# Microcontroller.net
KiCad netlist of a schematic drawn in Altium Designer
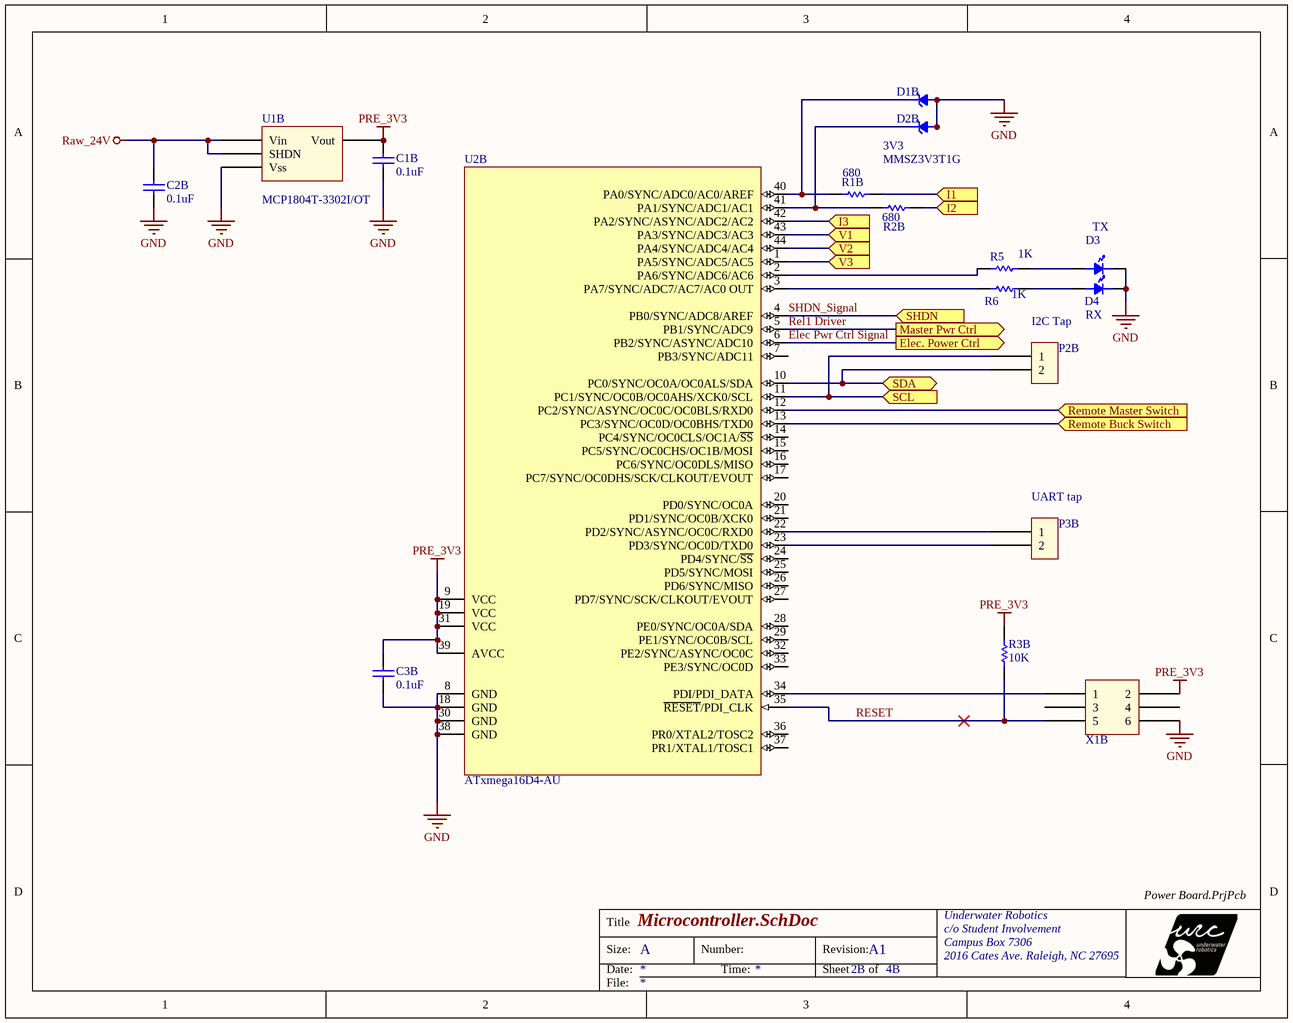
[diagram p0: Microcontroller.SchDoc]

(export (version "E")
  (design (tool "Eeschema 10.0.6"))
  (components
    (comp (ref "C1B")
      (value "0.1uF")
      (footprint "C0805")
      (description "Ceramic MLCC, AVX, X5R Dielectric")
      (fields
        (field (name "MANUFACTURER PART NUMBER") "08055C104JAT2A")
        (field (name "Comment") "0.1uF, C0805, AVX")
      )
      (libsource (lib "Capacitors SchLib") (part "0.1uF, C0805, AVX"))
    )
    (comp (ref "C2B")
      (value "0.1uF")
      (footprint "C0805")
      (description "Ceramic MLCC, AVX, X5R Dielectric")
      (fields
        (field (name "MANUFACTURER PART NUMBER") "08055C104JAT2A")
        (field (name "Comment") "0.1uF, C0805, AVX")
      )
      (libsource (lib "Capacitors SchLib") (part "0.1uF, C0805, AVX"))
    )
    (comp (ref "C3B")
      (value "0.1uF")
      (footprint "C0805")
      (description "Ceramic MLCC, AVX, X5R Dielectric")
      (fields
        (field (name "MANUFACTURER PART NUMBER") "08055C104JAT2A")
        (field (name "Comment") "0.1uF, C0805, AVX")
      )
      (libsource (lib "Capacitors SchLib") (part "0.1uF, C0805, AVX"))
    )
    (comp (ref "D1B")
      (value "3V3")
      (footprint "ONSC-SOD123-2-498_A_V")
      (description "3V3 Zener Diode")
      (fields
        (field (name "MANUFACTURER PART NUMBER") "MMSZ3V3T1G")
        (field (name "Comment") "MMSZ3V3T1G, 3V3 Zener Diode")
      )
      (libsource (lib "URC") (part "MMSZ3V3T1G, 3V3 Zener Diode"))
    )
    (comp (ref "D2B")
      (value "MMSZ3V3T1G, 3V3 Zener Diode")
      (footprint "ONSC-SOD123-2-498_A_V")
      (description "3V3 Zener Diode")
      (fields (field (name "MANUFACTURER PART NUMBER") "MMSZ3V3T1G"))
      (libsource (lib "URC") (part "MMSZ3V3T1G, 3V3 Zener Diode"))
    )
    (comp (ref "D3") (value "LED") (footprint "LED0805") (libsource (lib "URC_Lib") (part "LED")))
    (comp (ref "D4") (value "LED") (footprint "LED0805") (libsource (lib "URC_Lib") (part "LED")))
    (comp (ref "P2B")
      (value "Header")
      (footprint "1x2 Header")
      (description "1x2 Header")
      (libsource (lib "URC_Lib") (part "1x2 Header"))
    )
    (comp (ref "P3B")
      (value "Header")
      (footprint "1x2 Header")
      (description "1x2 Header")
      (libsource (lib "URC_Lib") (part "1x2 Header"))
    )
    (comp (ref "R1B")
      (value "680")
      (footprint "R0603")
      (description "Resistor")
      (fields (field (name "TOLERANCE") "5%") (field (name "MANUFACTURER PART NUMBER") "RC0603JR-07680RL"))
      (libsource (lib "Resistors SchLib") (part "680, 5%, 100mW, Yageo, R0603"))
    )
    (comp (ref "R2B")
      (value "680")
      (footprint "R0603")
      (description "Resistor")
      (fields (field (name "TOLERANCE") "5%") (field (name "MANUFACTURER PART NUMBER") "RC0603JR-07680RL"))
      (libsource (lib "Resistors SchLib") (part "680, 5%, 100mW, Yageo, R0603"))
    )
    (comp (ref "R3B")
      (value "10K")
      (footprint "R0603")
      (description "Resistor")
      (fields (field (name "TOLERANCE") "1%") (field (name "MANUFACTURER PART NUMBER") "RC0603FR-1010KL"))
      (libsource (lib "Resistors SchLib") (part "10k, 1%, 100mW, Yageo, R0603"))
    )
    (comp (ref "R5")
      (value "1K")
      (footprint "R0603")
      (description "Resistor")
      (fields (field (name "TOLERANCE") "5%") (field (name "MANUFACTURER PART NUMBER") "RC0603JR-131KL"))
      (libsource (lib "Resistors SchLib") (part "1k, 5%, 100mW, Yageo, R0603"))
    )
    (comp (ref "R6")
      (value "1K")
      (footprint "R0603")
      (description "Resistor")
      (fields (field (name "TOLERANCE") "5%") (field (name "MANUFACTURER PART NUMBER") "RC0603JR-131KL"))
      (libsource (lib "Resistors SchLib") (part "1k, 5%, 100mW, Yageo, R0603"))
    )
    (comp (ref "U1B")
      (value "MCP1804T-3302I/OT")
      (footprint "MCP1804T-3302I/OT")
      (description "3.3V Linear Regulator")
      (fields (field (name "MANUFACTURER PART NUMBER") "MCP1804T-3302I/OT"))
      (libsource (lib "URC") (part "MCP1804T-3302I/OT"))
    )
    (comp (ref "U2B")
      (value "ATxmega16D4-AU")
      (footprint "44A_N")
      (fields (field (name "MANUFACTURER PART NUMBER") "ATXMEGA16D4-AU"))
      (libsource (lib "Atmel Microcontroller AVR XMEGA") (part "ATxmega16D4-AU"))
    )
    (comp (ref "X1B")
      (value "Header")
      (footprint "2x3 Header")
      (description "2x3 Header")
      (fields (field (name "MANUFACTURER PART NUMBER") "67996-406HLF"))
      (libsource (lib "URC") (part "2x3 Header"))
    )
  )
  (nets
    (net (code "1") (name "/Elec Pwr Ctrl Signal") (class "Default")
      (node (ref "U2B") (pin "6") (pinfunction "PB2/SYNC/ASYNC/ADC10_6") (pintype "bidirectional"))
    )
    (net (code "2") (name "/I1") (class "Default")
      (node (ref "R1B") (pin "2") (pinfunction "2_2") (pintype "passive"))
    )
    (net (code "3") (name "/I2") (class "Default")
      (node (ref "R2B") (pin "2") (pinfunction "2_2") (pintype "passive"))
    )
    (net (code "4") (name "/I3") (class "Default")
      (node (ref "U2B") (pin "42") (pinfunction "PA2/SYNC/ASYNC/ADC2/AC2_42") (pintype "bidirectional"))
    )
    (net (code "5") (name "/RESET") (class "Default")
      (node (ref "R3B") (pin "1") (pinfunction "1_1") (pintype "passive"))
      (node (ref "U2B") (pin "35") (pinfunction "~{RESET}/PDI_CLK_35") (pintype "input"))
      (node (ref "X1B") (pin "5") (pinfunction "5_5") (pintype "passive"))
    )
    (net (code "6") (name "/Rel1 Driver") (class "Default")
      (node (ref "U2B") (pin "5") (pinfunction "PB1/SYNC/ADC9_5") (pintype "bidirectional"))
    )
    (net (code "7") (name "/Remote Buck Switch") (class "Default")
      (node (ref "U2B") (pin "13") (pinfunction "PC3/SYNC/OC0D/OC0BHS/TXD0_13") (pintype "bidirectional"))
    )
    (net (code "8") (name "/Remote Master Switch") (class "Default")
      (node (ref "U2B") (pin "12") (pinfunction "PC2/SYNC/ASYNC/OC0C/OC0BLS/RXD0_12") (pintype "bidirectional"))
    )
    (net (code "9") (name "/SCL") (class "Default")
      (node (ref "P2B") (pin "1") (pinfunction "1_1") (pintype "passive"))
      (node (ref "U2B") (pin "11") (pinfunction "PC1/SYNC/OC0B/OC0AHS/XCK0/SCL_11") (pintype "bidirectional"))
    )
    (net (code "10") (name "/SDA") (class "Default")
      (node (ref "P2B") (pin "2") (pinfunction "2_2") (pintype "passive"))
      (node (ref "U2B") (pin "10") (pinfunction "PC0/SYNC/OC0A/OC0ALS/SDA_10") (pintype "bidirectional"))
    )
    (net (code "11") (name "/SHDN_Signal") (class "Default")
      (node (ref "U2B") (pin "4") (pinfunction "PB0/SYNC/ADC8/AREF_4") (pintype "bidirectional"))
    )
    (net (code "12") (name "/V1") (class "Default")
      (node (ref "U2B") (pin "43") (pinfunction "PA3/SYNC/ADC3/AC3_43") (pintype "bidirectional"))
    )
    (net (code "13") (name "/V2") (class "Default")
      (node (ref "U2B") (pin "44") (pinfunction "PA4/SYNC/ADC4/AC4_44") (pintype "bidirectional"))
    )
    (net (code "14") (name "/V3") (class "Default")
      (node (ref "U2B") (pin "1") (pinfunction "PA5/SYNC/ADC5/AC5_1") (pintype "bidirectional"))
    )
    (net (code "15") (name "GND") (class "Default")
      (node (ref "C1B") (pin "2") (pinfunction "2_2") (pintype "passive"))
      (node (ref "C2B") (pin "2") (pinfunction "2_2") (pintype "passive"))
      (node (ref "C3B") (pin "2") (pinfunction "2_2") (pintype "passive"))
      (node (ref "D1B") (pin "A") (pinfunction "2_A") (pintype "passive"))
      (node (ref "D2B") (pin "A") (pinfunction "1_A") (pintype "passive"))
      (node (ref "D3") (pin "1") (pinfunction "1_1") (pintype "passive"))
      (node (ref "D4") (pin "1") (pinfunction "1_1") (pintype "passive"))
      (node (ref "U1B") (pin "Vss") (pinfunction "Vss_Vss") (pintype "passive"))
      (node (ref "U2B") (pin "18") (pinfunction "GND_18") (pintype "power_in"))
      (node (ref "U2B") (pin "30") (pinfunction "GND_30") (pintype "power_in"))
      (node (ref "U2B") (pin "38") (pinfunction "GND_38") (pintype "power_in"))
      (node (ref "U2B") (pin "8") (pinfunction "GND_8") (pintype "power_in"))
      (node (ref "X1B") (pin "6") (pinfunction "6_6") (pintype "passive"))
    )
    (net (code "16") (name "Net-(D3-Pad2)") (class "Default")
      (node (ref "D3") (pin "2") (pinfunction "2_2") (pintype "passive"))
      (node (ref "R5") (pin "2") (pinfunction "2_2") (pintype "passive"))
    )
    (net (code "17") (name "Net-(D4-Pad2)") (class "Default")
      (node (ref "D4") (pin "2") (pinfunction "2_2") (pintype "passive"))
      (node (ref "R6") (pin "2") (pinfunction "2_2") (pintype "passive"))
    )
    (net (code "18") (name "Net-(U2B-PA0{slash}SYNC{slash}ADC0{slash}AC0{slash}AREF)") (class "Default")
      (node (ref "D1B") (pin "K") (pinfunction "2_K") (pintype "passive"))
      (node (ref "R1B") (pin "1") (pinfunction "1_1") (pintype "passive"))
      (node (ref "U2B") (pin "40") (pinfunction "PA0/SYNC/ADC0/AC0/AREF_40") (pintype "bidirectional"))
    )
    (net (code "19") (name "Net-(U2B-PA1{slash}SYNC{slash}ADC1{slash}AC1)") (class "Default")
      (node (ref "D2B") (pin "K") (pinfunction "2_K") (pintype "passive"))
      (node (ref "R2B") (pin "1") (pinfunction "1_1") (pintype "passive"))
      (node (ref "U2B") (pin "41") (pinfunction "PA1/SYNC/ADC1/AC1_41") (pintype "bidirectional"))
    )
    (net (code "20") (name "Net-(U2B-PA6{slash}SYNC{slash}ADC6{slash}AC6)") (class "Default")
      (node (ref "R5") (pin "1") (pinfunction "1_1") (pintype "passive"))
      (node (ref "U2B") (pin "2") (pinfunction "PA6/SYNC/ADC6/AC6_2") (pintype "bidirectional"))
    )
    (net (code "21") (name "Net-(U2B-PA7{slash}SYNC{slash}ADC7{slash}AC7{slash}AC0_OUT)") (class "Default")
      (node (ref "R6") (pin "1") (pinfunction "1_1") (pintype "passive"))
      (node (ref "U2B") (pin "3") (pinfunction "PA7/SYNC/ADC7/AC7/AC0_OUT_3") (pintype "bidirectional"))
    )
    (net (code "22") (name "Net-(U2B-PD2{slash}SYNC{slash}ASYNC{slash}OC0C{slash}RXD0)") (class "Default")
      (node (ref "P3B") (pin "1") (pinfunction "1_1") (pintype "passive"))
      (node (ref "U2B") (pin "22") (pinfunction "PD2/SYNC/ASYNC/OC0C/RXD0_22") (pintype "bidirectional"))
    )
    (net (code "23") (name "Net-(U2B-PD3{slash}SYNC{slash}OC0D{slash}TXD0)") (class "Default")
      (node (ref "P3B") (pin "2") (pinfunction "2_2") (pintype "passive"))
      (node (ref "U2B") (pin "23") (pinfunction "PD3/SYNC/OC0D/TXD0_23") (pintype "bidirectional"))
    )
    (net (code "24") (name "Net-(U2B-PDI{slash}PDI_DATA)") (class "Default")
      (node (ref "U2B") (pin "34") (pinfunction "PDI/PDI_DATA_34") (pintype "bidirectional"))
      (node (ref "X1B") (pin "1") (pinfunction "1_1") (pintype "passive"))
    )
    (net (code "25") (name "PRE_3V3") (class "Default")
      (node (ref "C1B") (pin "1") (pinfunction "+_1") (pintype "passive"))
      (node (ref "C3B") (pin "1") (pinfunction "+_1") (pintype "passive"))
      (node (ref "R3B") (pin "2") (pinfunction "2_2") (pintype "passive"))
      (node (ref "U1B") (pin "Vout") (pinfunction "Vout_Vout") (pintype "passive"))
      (node (ref "U2B") (pin "19") (pinfunction "VCC_19") (pintype "power_in"))
      (node (ref "U2B") (pin "31") (pinfunction "VCC_31") (pintype "power_in"))
      (node (ref "U2B") (pin "39") (pinfunction "AVCC_39") (pintype "power_in"))
      (node (ref "U2B") (pin "9") (pinfunction "VCC_9") (pintype "power_in"))
      (node (ref "X1B") (pin "2") (pinfunction "2_2") (pintype "passive"))
    )
    (net (code "26") (name "Raw_24V") (class "Default")
      (node (ref "C2B") (pin "1") (pinfunction "+_1") (pintype "passive"))
      (node (ref "U1B") (pin "SHDN") (pinfunction "SHDN_SHDN") (pintype "passive"))
      (node (ref "U1B") (pin "Vin") (pinfunction "Vin_Vin") (pintype "passive"))
    )
    (net (code "27") (name "unconnected-(U2B-PB3{slash}SYNC{slash}ADC11-Pad7)") (class "Default")
      (node (ref "U2B") (pin "7") (pinfunction "PB3/SYNC/ADC11_7") (pintype "bidirectional"))
    )
    (net (code "28") (name "unconnected-(U2B-PC4{slash}SYNC{slash}OC0CLS{slash}OC1A{slash}~{SS}-Pad14)") (class "Default")
      (node (ref "U2B") (pin "14") (pinfunction "PC4/SYNC/OC0CLS/OC1A/~{SS}_14") (pintype "bidirectional"))
    )
    (net (code "29") (name "unconnected-(U2B-PC5{slash}SYNC{slash}OC0CHS{slash}OC1B{slash}MOSI-Pad15)") (class "Default")
      (node (ref "U2B") (pin "15") (pinfunction "PC5/SYNC/OC0CHS/OC1B/MOSI_15") (pintype "bidirectional"))
    )
    (net (code "30") (name "unconnected-(U2B-PC6{slash}SYNC{slash}OC0DLS{slash}MISO-Pad16)") (class "Default")
      (node (ref "U2B") (pin "16") (pinfunction "PC6/SYNC/OC0DLS/MISO_16") (pintype "bidirectional"))
    )
    (net (code "31") (name "unconnected-(U2B-PC7{slash}SYNC{slash}OC0DHS{slash}SCK{slash}CLKOUT{slash}EVOUT-Pad17)") (class "Default")
      (node (ref "U2B") (pin "17") (pinfunction "PC7/SYNC/OC0DHS/SCK/CLKOUT/EVOUT_17") (pintype "bidirectional"))
    )
    (net (code "32") (name "unconnected-(U2B-PD0{slash}SYNC{slash}OC0A-Pad20)") (class "Default")
      (node (ref "U2B") (pin "20") (pinfunction "PD0/SYNC/OC0A_20") (pintype "bidirectional"))
    )
    (net (code "33") (name "unconnected-(U2B-PD1{slash}SYNC{slash}OC0B{slash}XCK0-Pad21)") (class "Default")
      (node (ref "U2B") (pin "21") (pinfunction "PD1/SYNC/OC0B/XCK0_21") (pintype "bidirectional"))
    )
    (net (code "34") (name "unconnected-(U2B-PD4{slash}SYNC{slash}~{SS}-Pad24)") (class "Default")
      (node (ref "U2B") (pin "24") (pinfunction "PD4/SYNC/~{SS}_24") (pintype "bidirectional"))
    )
    (net (code "35") (name "unconnected-(U2B-PD5{slash}SYNC{slash}MOSI-Pad25)") (class "Default")
      (node (ref "U2B") (pin "25") (pinfunction "PD5/SYNC/MOSI_25") (pintype "bidirectional"))
    )
    (net (code "36") (name "unconnected-(U2B-PD6{slash}SYNC{slash}MISO-Pad26)") (class "Default")
      (node (ref "U2B") (pin "26") (pinfunction "PD6/SYNC/MISO_26") (pintype "bidirectional"))
    )
    (net (code "37") (name "unconnected-(U2B-PD7{slash}SYNC{slash}SCK{slash}CLKOUT{slash}EVOUT-Pad27)") (class "Default")
      (node (ref "U2B") (pin "27") (pinfunction "PD7/SYNC/SCK/CLKOUT/EVOUT_27") (pintype "bidirectional"))
    )
    (net (code "38") (name "unconnected-(U2B-PE0{slash}SYNC{slash}OC0A{slash}SDA-Pad28)") (class "Default")
      (node (ref "U2B") (pin "28") (pinfunction "PE0/SYNC/OC0A/SDA_28") (pintype "bidirectional"))
    )
    (net (code "39") (name "unconnected-(U2B-PE1{slash}SYNC{slash}OC0B{slash}SCL-Pad29)") (class "Default")
      (node (ref "U2B") (pin "29") (pinfunction "PE1/SYNC/OC0B/SCL_29") (pintype "bidirectional"))
    )
    (net (code "40") (name "unconnected-(U2B-PE2{slash}SYNC{slash}ASYNC{slash}OC0C-Pad32)") (class "Default")
      (node (ref "U2B") (pin "32") (pinfunction "PE2/SYNC/ASYNC/OC0C_32") (pintype "bidirectional"))
    )
    (net (code "41") (name "unconnected-(U2B-PE3{slash}SYNC{slash}OC0D-Pad33)") (class "Default")
      (node (ref "U2B") (pin "33") (pinfunction "PE3/SYNC/OC0D_33") (pintype "bidirectional"))
    )
    (net (code "42") (name "unconnected-(U2B-PR0{slash}XTAL2{slash}TOSC2-Pad36)") (class "Default")
      (node (ref "U2B") (pin "36") (pinfunction "PR0/XTAL2/TOSC2_36") (pintype "bidirectional"))
    )
    (net (code "43") (name "unconnected-(U2B-PR1{slash}XTAL1{slash}TOSC1-Pad37)") (class "Default")
      (node (ref "U2B") (pin "37") (pinfunction "PR1/XTAL1/TOSC1_37") (pintype "bidirectional"))
    )
    (net (code "44") (name "unconnected-(X1B-Pad3)") (class "Default")
      (node (ref "X1B") (pin "3") (pinfunction "3_3") (pintype "passive"))
    )
    (net (code "45") (name "unconnected-(X1B-Pad4)") (class "Default")
      (node (ref "X1B") (pin "4") (pinfunction "4_4") (pintype "passive"))
    )
  )
)
